# RELAY11.net
KiCad netlist of a schematic drawn in Altium Designer
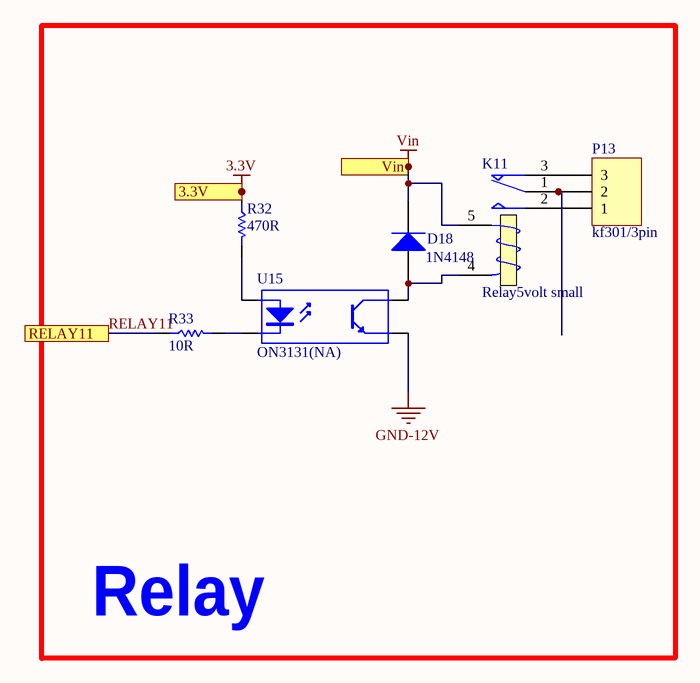
[diagram p0: RELAY11.SchDoc]

(export (version "E")
  (design (tool "Eeschema 10.0.6"))
  (components
    (comp (ref "D18")
      (value "1N4148")
      (footprint "sod123")
      (description "1 Amp General Purpose Rectifier")
      (fields (field (name "PUBLISHER") "Altium Limited"))
      (libsource (lib "Miscellaneous Devices") (part "Diode 1N4007"))
    )
    (comp (ref "K11")
      (value "Relay5volt small")
      (footprint "relay5_childern")
      (description "SPDT Relay")
      (fields (field (name "PUBLISHER") "Altium Limited"))
      (libsource (lib "FLIB") (part "Relay"))
    )
    (comp (ref "P13")
      (value "kf301/3pin")
      (footprint "Blue Connector 1*3 -kf301")
      (fields (field (name "PUBLISHER") "Altium Limited"))
      (libsource (lib "Miscellaneous Connectors") (part "Header 3"))
    )
    (comp (ref "R32")
      (value "470R")
      (footprint "0805/resistor")
      (description "Resistor")
      (fields (field (name "TOLERANCE") "5%") (field (name "POWER") "1/8 W"))
      (libsource (lib "skille") (part "Resistor"))
    )
    (comp (ref "R33")
      (value "10R")
      (footprint "0805/resistor")
      (description "Resistor")
      (fields (field (name "TOLERANCE") "5%") (field (name "POWER") "1/8 W"))
      (libsource (lib "skille") (part "Resistor"))
    )
    (comp (ref "U15")
      (value "ON3131(NA)")
      (footprint "OPTO_COUPLER")
      (description "4-Pin Phototransistor Optocoupler")
      (fields (field (name "PUBLISHER") "Altium Limited"))
      (libsource (lib "skille") (part "Optoisolator1"))
    )
  )
  (nets
    (net (code "1") (name "/RELAY11") (class "Default")
      (node (ref "R33") (pin "1") (pinfunction "1_1") (pintype "passive"))
    )
    (net (code "2") (name "3.3V") (class "Default")
      (node (ref "R32") (pin "1") (pinfunction "1_1") (pintype "passive"))
    )
    (net (code "3") (name "GND-12V") (class "Default")
      (node (ref "U15") (pin "3") (pinfunction "E_3") (pintype "passive"))
    )
    (net (code "4") (name "Net-(K11-COM)") (class "Default")
      (node (ref "K11") (pin "1") (pinfunction "COM_1") (pintype "passive"))
      (node (ref "P13") (pin "2") (pinfunction "2_2") (pintype "passive"))
    )
    (net (code "5") (name "Net-(K11-NO)") (class "Default")
      (node (ref "K11") (pin "2") (pinfunction "NO_2") (pintype "passive"))
      (node (ref "P13") (pin "1") (pinfunction "1_1") (pintype "passive"))
    )
    (net (code "6") (name "Net-(K11-T1)") (class "Default")
      (node (ref "K11") (pin "3") (pinfunction "T1_3") (pintype "passive"))
      (node (ref "P13") (pin "3") (pinfunction "3_3") (pintype "passive"))
    )
    (net (code "7") (name "Net-(K11-T2)") (class "Default")
      (node (ref "D18") (pin "A") (pinfunction "A_A") (pintype "passive"))
      (node (ref "K11") (pin "4") (pinfunction "T2_4") (pintype "passive"))
      (node (ref "U15") (pin "4") (pinfunction "C_4") (pintype "passive"))
    )
    (net (code "8") (name "Net-(U15-A)") (class "Default")
      (node (ref "R32") (pin "2") (pinfunction "2_2") (pintype "passive"))
      (node (ref "U15") (pin "1") (pinfunction "A_1") (pintype "passive"))
    )
    (net (code "9") (name "Net-(U15-K)") (class "Default")
      (node (ref "R33") (pin "2") (pinfunction "2_2") (pintype "passive"))
      (node (ref "U15") (pin "2") (pinfunction "K_2") (pintype "passive"))
    )
    (net (code "10") (name "Vin") (class "Default")
      (node (ref "D18") (pin "K") (pinfunction "K_K") (pintype "passive"))
      (node (ref "K11") (pin "5") (pinfunction "5_5") (pintype "passive"))
    )
  )
)
